# mcu.net
KiCad netlist of a schematic drawn in Altium Designer
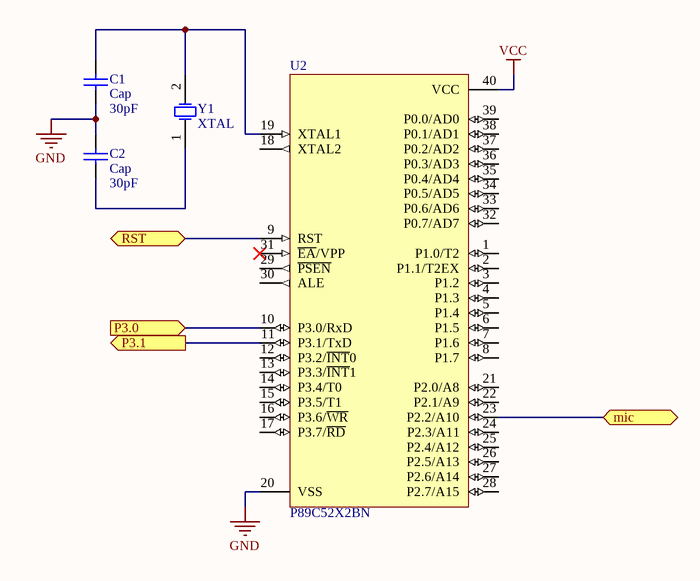
[diagram p0: mcu.SchDoc]

(export (version "E")
  (design (tool "Eeschema 10.0.6"))
  (components
    (comp (ref "C1")
      (value "Cap")
      (footprint "RAD-0.3")
      (description "Capacitor")
      (fields (field (name "ALTIUM_VALUE") "30pF") (field (name "PUBLISHER") "Altium Limited"))
      (libsource (lib "Miscellaneous Devices") (part "Cap"))
    )
    (comp (ref "C2")
      (value "Cap")
      (footprint "RAD-0.3")
      (description "Capacitor")
      (fields (field (name "ALTIUM_VALUE") "30pF") (field (name "PUBLISHER") "Altium Limited"))
      (libsource (lib "Miscellaneous Devices") (part "Cap"))
    )
    (comp (ref "U2")
      (value "P89C52X2BN")
      (footprint "SOT129-1")
      (description "80C51 8-Bit Flash Microcontroller Family, 8 kB Flash")
      (fields (field (name "PUBLISHER") "Altium Limited"))
      (libsource (lib "Philips Microcontroller 8-Bit") (part "P89C52X2BN"))
    )
    (comp (ref "Y1")
      (value "XTAL")
      (footprint "R38")
      (description "Crystal Oscillator")
      (fields (field (name "PUBLISHER") "Altium Limited"))
      (libsource (lib "Miscellaneous Devices") (part "XTAL"))
    )
  )
  (nets
    (net (code "1") (name "/P3.0") (class "Default")
      (node (ref "U2") (pin "10") (pinfunction "P3.0/RxD_10") (pintype "bidirectional"))
    )
    (net (code "2") (name "/P3.1") (class "Default")
      (node (ref "U2") (pin "11") (pinfunction "P3.1/TxD_11") (pintype "bidirectional"))
    )
    (net (code "3") (name "/RST") (class "Default")
      (node (ref "U2") (pin "9") (pinfunction "RST_9") (pintype "input"))
    )
    (net (code "4") (name "/mic") (class "Default")
      (node (ref "U2") (pin "23") (pinfunction "P2.2/A10_23") (pintype "bidirectional"))
    )
    (net (code "5") (name "GND") (class "Default")
      (node (ref "C1") (pin "1") (pinfunction "1_1") (pintype "passive"))
      (node (ref "C2") (pin "2") (pinfunction "2_2") (pintype "passive"))
      (node (ref "U2") (pin "20") (pinfunction "VSS_20") (pintype "power_in"))
    )
    (net (code "6") (name "Net-(U2-XTAL1)") (class "Default")
      (node (ref "C1") (pin "2") (pinfunction "2_2") (pintype "passive"))
      (node (ref "U2") (pin "19") (pinfunction "XTAL1_19") (pintype "input"))
      (node (ref "Y1") (pin "2") (pinfunction "OSC2_2") (pintype "passive"))
    )
    (net (code "7") (name "Net-(Y1-OSC1)") (class "Default")
      (node (ref "C2") (pin "1") (pinfunction "1_1") (pintype "passive"))
      (node (ref "Y1") (pin "1") (pinfunction "OSC1_1") (pintype "passive"))
    )
    (net (code "8") (name "VCC") (class "Default")
      (node (ref "U2") (pin "40") (pinfunction "VCC_40") (pintype "power_in"))
    )
    (net (code "9") (name "unconnected-(U2-ALE-Pad30)") (class "Default")
      (node (ref "U2") (pin "30") (pinfunction "ALE_30") (pintype "output"))
    )
    (net (code "10") (name "unconnected-(U2-P0.0{slash}AD0-Pad39)") (class "Default")
      (node (ref "U2") (pin "39") (pinfunction "P0.0/AD0_39") (pintype "bidirectional"))
    )
    (net (code "11") (name "unconnected-(U2-P0.1{slash}AD1-Pad38)") (class "Default")
      (node (ref "U2") (pin "38") (pinfunction "P0.1/AD1_38") (pintype "bidirectional"))
    )
    (net (code "12") (name "unconnected-(U2-P0.2{slash}AD2-Pad37)") (class "Default")
      (node (ref "U2") (pin "37") (pinfunction "P0.2/AD2_37") (pintype "bidirectional"))
    )
    (net (code "13") (name "unconnected-(U2-P0.3{slash}AD3-Pad36)") (class "Default")
      (node (ref "U2") (pin "36") (pinfunction "P0.3/AD3_36") (pintype "bidirectional"))
    )
    (net (code "14") (name "unconnected-(U2-P0.4{slash}AD4-Pad35)") (class "Default")
      (node (ref "U2") (pin "35") (pinfunction "P0.4/AD4_35") (pintype "bidirectional"))
    )
    (net (code "15") (name "unconnected-(U2-P0.5{slash}AD5-Pad34)") (class "Default")
      (node (ref "U2") (pin "34") (pinfunction "P0.5/AD5_34") (pintype "bidirectional"))
    )
    (net (code "16") (name "unconnected-(U2-P0.6{slash}AD6-Pad33)") (class "Default")
      (node (ref "U2") (pin "33") (pinfunction "P0.6/AD6_33") (pintype "bidirectional"))
    )
    (net (code "17") (name "unconnected-(U2-P0.7{slash}AD7-Pad32)") (class "Default")
      (node (ref "U2") (pin "32") (pinfunction "P0.7/AD7_32") (pintype "bidirectional"))
    )
    (net (code "18") (name "unconnected-(U2-P1.0{slash}T2-Pad1)") (class "Default")
      (node (ref "U2") (pin "1") (pinfunction "P1.0/T2_1") (pintype "bidirectional"))
    )
    (net (code "19") (name "unconnected-(U2-P1.1{slash}T2EX-Pad2)") (class "Default")
      (node (ref "U2") (pin "2") (pinfunction "P1.1/T2EX_2") (pintype "bidirectional"))
    )
    (net (code "20") (name "unconnected-(U2-P1.2-Pad3)") (class "Default")
      (node (ref "U2") (pin "3") (pinfunction "P1.2_3") (pintype "bidirectional"))
    )
    (net (code "21") (name "unconnected-(U2-P1.3-Pad4)") (class "Default")
      (node (ref "U2") (pin "4") (pinfunction "P1.3_4") (pintype "bidirectional"))
    )
    (net (code "22") (name "unconnected-(U2-P1.4-Pad5)") (class "Default")
      (node (ref "U2") (pin "5") (pinfunction "P1.4_5") (pintype "bidirectional"))
    )
    (net (code "23") (name "unconnected-(U2-P1.5-Pad6)") (class "Default")
      (node (ref "U2") (pin "6") (pinfunction "P1.5_6") (pintype "bidirectional"))
    )
    (net (code "24") (name "unconnected-(U2-P1.6-Pad7)") (class "Default")
      (node (ref "U2") (pin "7") (pinfunction "P1.6_7") (pintype "bidirectional"))
    )
    (net (code "25") (name "unconnected-(U2-P1.7-Pad8)") (class "Default")
      (node (ref "U2") (pin "8") (pinfunction "P1.7_8") (pintype "bidirectional"))
    )
    (net (code "26") (name "unconnected-(U2-P2.0{slash}A8-Pad21)") (class "Default")
      (node (ref "U2") (pin "21") (pinfunction "P2.0/A8_21") (pintype "bidirectional"))
    )
    (net (code "27") (name "unconnected-(U2-P2.1{slash}A9-Pad22)") (class "Default")
      (node (ref "U2") (pin "22") (pinfunction "P2.1/A9_22") (pintype "bidirectional"))
    )
    (net (code "28") (name "unconnected-(U2-P2.3{slash}A11-Pad24)") (class "Default")
      (node (ref "U2") (pin "24") (pinfunction "P2.3/A11_24") (pintype "bidirectional"))
    )
    (net (code "29") (name "unconnected-(U2-P2.4{slash}A12-Pad25)") (class "Default")
      (node (ref "U2") (pin "25") (pinfunction "P2.4/A12_25") (pintype "bidirectional"))
    )
    (net (code "30") (name "unconnected-(U2-P2.5{slash}A13-Pad26)") (class "Default")
      (node (ref "U2") (pin "26") (pinfunction "P2.5/A13_26") (pintype "bidirectional"))
    )
    (net (code "31") (name "unconnected-(U2-P2.6{slash}A14-Pad27)") (class "Default")
      (node (ref "U2") (pin "27") (pinfunction "P2.6/A14_27") (pintype "bidirectional"))
    )
    (net (code "32") (name "unconnected-(U2-P2.7{slash}A15-Pad28)") (class "Default")
      (node (ref "U2") (pin "28") (pinfunction "P2.7/A15_28") (pintype "bidirectional"))
    )
    (net (code "33") (name "unconnected-(U2-P3.2{slash}~{INT}0-Pad12)") (class "Default")
      (node (ref "U2") (pin "12") (pinfunction "P3.2/~{INT}0_12") (pintype "bidirectional"))
    )
    (net (code "34") (name "unconnected-(U2-P3.3{slash}~{INT}1-Pad13)") (class "Default")
      (node (ref "U2") (pin "13") (pinfunction "P3.3/~{INT}1_13") (pintype "bidirectional"))
    )
    (net (code "35") (name "unconnected-(U2-P3.4{slash}T0-Pad14)") (class "Default")
      (node (ref "U2") (pin "14") (pinfunction "P3.4/T0_14") (pintype "bidirectional"))
    )
    (net (code "36") (name "unconnected-(U2-P3.5{slash}T1-Pad15)") (class "Default")
      (node (ref "U2") (pin "15") (pinfunction "P3.5/T1_15") (pintype "bidirectional"))
    )
    (net (code "37") (name "unconnected-(U2-P3.6{slash}~{WR}-Pad16)") (class "Default")
      (node (ref "U2") (pin "16") (pinfunction "P3.6/~{WR}_16") (pintype "bidirectional"))
    )
    (net (code "38") (name "unconnected-(U2-P3.7{slash}~{RD}-Pad17)") (class "Default")
      (node (ref "U2") (pin "17") (pinfunction "P3.7/~{RD}_17") (pintype "bidirectional"))
    )
    (net (code "39") (name "unconnected-(U2-XTAL2-Pad18)") (class "Default")
      (node (ref "U2") (pin "18") (pinfunction "XTAL2_18") (pintype "output"))
    )
    (net (code "40") (name "unconnected-(U2-~{EA}{slash}VPP-Pad31)") (class "Default")
      (node (ref "U2") (pin "31") (pinfunction "~{EA}/VPP_31") (pintype "input+no_connect"))
    )
    (net (code "41") (name "unconnected-(U2-~{PSEN}-Pad29)") (class "Default")
      (node (ref "U2") (pin "29") (pinfunction "~{PSEN}_29") (pintype "output"))
    )
  )
)
